# bluetooth_adapter.net
KiCad netlist of a schematic drawn in EAGLE
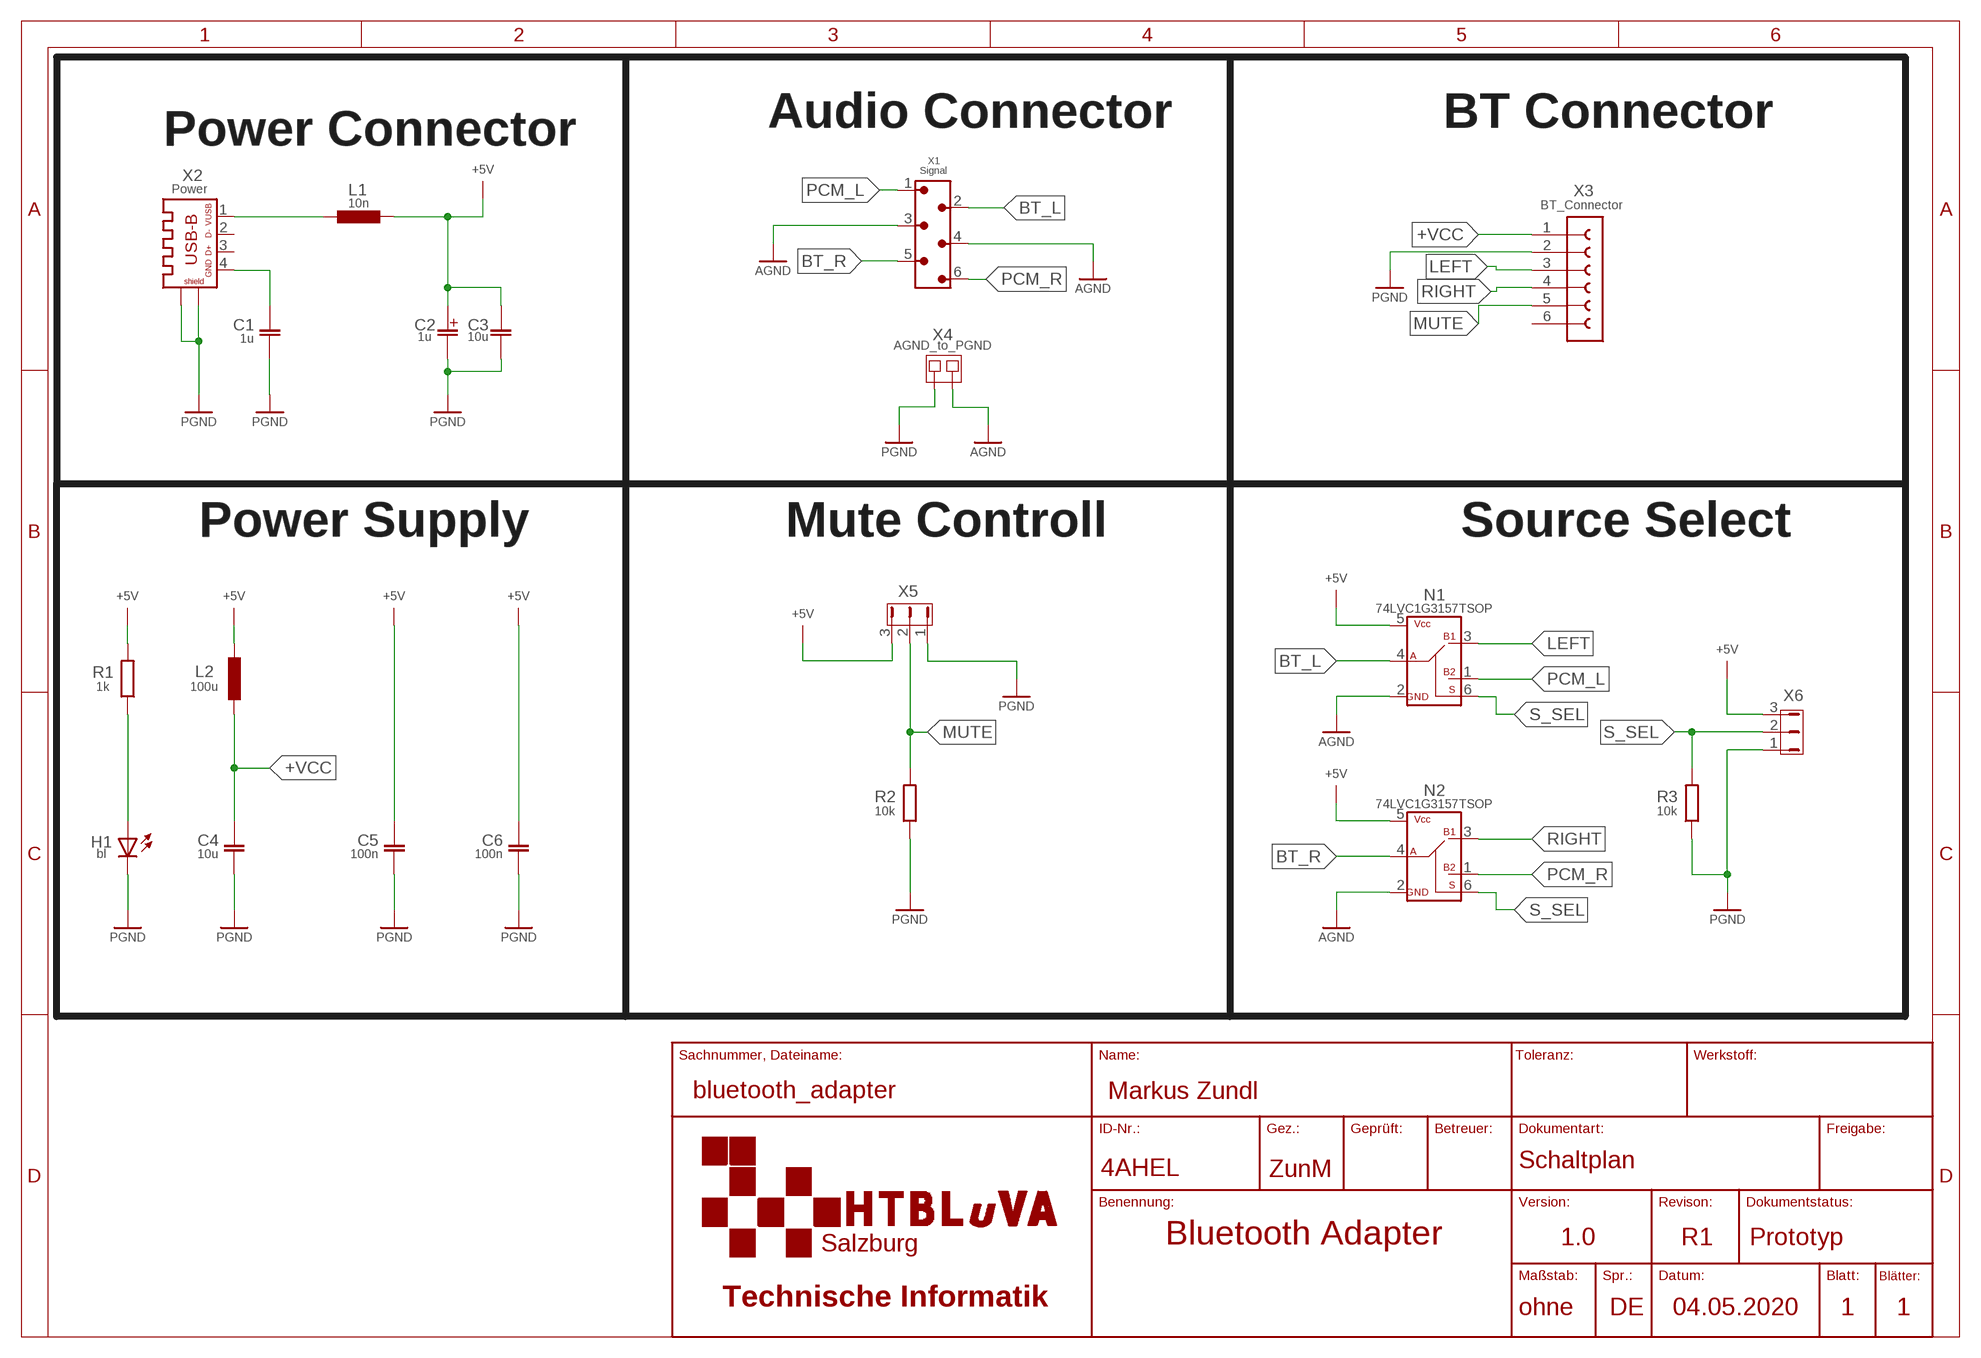
[diagram p0: schematic, sheet 1]

(export (version "E")
  (design (tool "Eeschema 10.0.6"))
  (components
    (comp (ref "C1")
      (value "1u")
      (footprint "eagle-import:C3216")
      (libsource (lib "eagle-import") (part "C-EUC3216"))
    )
    (comp (ref "C2")
      (value "1u")
      (footprint "eagle-import:A_3216-18R")
      (libsource (lib "eagle-import") (part "CPOL-EUA/3216-18R"))
    )
    (comp (ref "C3")
      (value "10u")
      (footprint "eagle-import:C3216")
      (libsource (lib "eagle-import") (part "C-EUC3216"))
    )
    (comp (ref "C4")
      (value "10u")
      (footprint "eagle-import:C3216")
      (libsource (lib "eagle-import") (part "C-EUC3216"))
    )
    (comp (ref "C5")
      (value "100n")
      (footprint "eagle-import:C3216")
      (libsource (lib "eagle-import") (part "C-EUC3216"))
    )
    (comp (ref "C6")
      (value "100n")
      (footprint "eagle-import:C3216")
      (libsource (lib "eagle-import") (part "C-EUC3216"))
    )
    (comp (ref "H1")
      (value "bl")
      (footprint "eagle-import:CHIPLED_0805")
      (libsource (lib "eagle-import") (part "LEDCHIPLED_0805"))
    )
    (comp (ref "L1")
      (value "10n")
      (footprint "eagle-import:L1210")
      (libsource (lib "eagle-import") (part "L-EUL1210"))
    )
    (comp (ref "L2")
      (value "100u")
      (footprint "eagle-import:L0805")
      (libsource (lib "eagle-import") (part "L-EUL0805"))
    )
    (comp (ref "N1")
      (value "74LVC1G3157TSOP")
      (footprint "eagle-import:TSOP6")
      (libsource (lib "eagle-import") (part "74LVC1G3157TSOP"))
    )
    (comp (ref "N2")
      (value "74LVC1G3157TSOP")
      (footprint "eagle-import:TSOP6")
      (libsource (lib "eagle-import") (part "74LVC1G3157TSOP"))
    )
    (comp (ref "R1")
      (value "1k")
      (footprint "eagle-import:R0805")
      (libsource (lib "eagle-import") (part "R-EU_R0805"))
    )
    (comp (ref "R2")
      (value "10k")
      (footprint "eagle-import:R0805")
      (libsource (lib "eagle-import") (part "R-EU_R0805"))
    )
    (comp (ref "R3")
      (value "10k")
      (footprint "eagle-import:R0805")
      (libsource (lib "eagle-import") (part "R-EU_R0805"))
    )
    (comp (ref "X1")
      (value "Signal")
      (footprint "eagle-import:690357100672")
      (libsource (lib "eagle-import") (part "WUERT_BUCHSE_6POL"))
    )
    (comp (ref "X2")
      (value "Power")
      (footprint "eagle-import:MYLIB_USB-B-LUM")
      (libsource (lib "eagle-import") (part "USB-B_432411"))
    )
    (comp (ref "X3")
      (value "BT_Connector")
      (footprint "eagle-import:MYCONNECTORS_FE-1X6_BDIA")
      (libsource (lib "eagle-import") (part "CONNECTORS_FEMHD-1X61X6_BDIA"))
    )
    (comp (ref "X4")
      (value "AGND_to_PGND")
      (footprint "eagle-import:MYLIB_SJ")
      (libsource (lib "eagle-import") (part "JUMPSMD1FACH-1"))
    )
    (comp (ref "X5")
      (value "JP2E")
      (footprint "eagle-import:MYLIB_JP2")
      (libsource (lib "eagle-import") (part "JP2E"))
    )
    (comp (ref "X6")
      (value "JP2E")
      (footprint "eagle-import:MYLIB_JP2")
      (libsource (lib "eagle-import") (part "JP2E"))
    )
  )
  (nets
    (net (code "1") (name "+5V") (class "Default")
      (node (ref "C2") (pin "+") (pinfunction "+_+") (pintype "passive"))
      (node (ref "C3") (pin "1") (pinfunction "1_1") (pintype "passive"))
      (node (ref "C5") (pin "1") (pinfunction "1_1") (pintype "passive"))
      (node (ref "C6") (pin "1") (pinfunction "1_1") (pintype "passive"))
      (node (ref "L1") (pin "2") (pinfunction "2_2") (pintype "passive"))
      (node (ref "L2") (pin "2") (pinfunction "2_2") (pintype "passive"))
      (node (ref "N1") (pin "5") (pinfunction "VCC_5") (pintype "bidirectional"))
      (node (ref "N2") (pin "5") (pinfunction "VCC_5") (pintype "bidirectional"))
      (node (ref "R1") (pin "2") (pinfunction "2_2") (pintype "passive"))
      (node (ref "X5") (pin "3") (pinfunction "3_3") (pintype "passive"))
      (node (ref "X6") (pin "3") (pinfunction "3_3") (pintype "passive"))
    )
    (net (code "2") (name "+VCC") (class "Default")
      (node (ref "C4") (pin "1") (pinfunction "1_1") (pintype "passive"))
      (node (ref "L2") (pin "1") (pinfunction "1_1") (pintype "passive"))
      (node (ref "X3") (pin "1") (pinfunction "1_1") (pintype "passive"))
    )
    (net (code "3") (name "AGND") (class "Default")
      (node (ref "N1") (pin "2") (pinfunction "GND_2") (pintype "bidirectional"))
      (node (ref "N2") (pin "2") (pinfunction "GND_2") (pintype "bidirectional"))
      (node (ref "X1") (pin "3") (pinfunction "3_3") (pintype "passive"))
      (node (ref "X1") (pin "4") (pinfunction "4_4") (pintype "passive"))
      (node (ref "X4") (pin "2") (pinfunction "2_2") (pintype "passive"))
    )
    (net (code "4") (name "BT_L") (class "Default")
      (node (ref "N1") (pin "4") (pinfunction "A_4") (pintype "bidirectional"))
      (node (ref "X1") (pin "2") (pinfunction "2_2") (pintype "passive"))
    )
    (net (code "5") (name "BT_R") (class "Default")
      (node (ref "N2") (pin "4") (pinfunction "A_4") (pintype "bidirectional"))
      (node (ref "X1") (pin "5") (pinfunction "5_5") (pintype "passive"))
    )
    (net (code "6") (name "LEFT") (class "Default")
      (node (ref "N1") (pin "3") (pinfunction "B1_3") (pintype "bidirectional"))
      (node (ref "X3") (pin "3") (pinfunction "3_3") (pintype "passive"))
    )
    (net (code "7") (name "MUTE") (class "Default")
      (node (ref "R2") (pin "2") (pinfunction "2_2") (pintype "passive"))
      (node (ref "X3") (pin "5") (pinfunction "5_5") (pintype "passive"))
      (node (ref "X5") (pin "2") (pinfunction "2_2") (pintype "passive"))
    )
    (net (code "8") (name "Net-(C1-Pad1)") (class "Default")
      (node (ref "C1") (pin "1") (pinfunction "1_1") (pintype "passive"))
      (node (ref "X2") (pin "4") (pinfunction "4_4") (pintype "passive"))
    )
    (net (code "9") (name "Net-(H1-PadA)") (class "Default")
      (node (ref "H1") (pin "A") (pinfunction "A_A") (pintype "passive"))
      (node (ref "R1") (pin "1") (pinfunction "1_1") (pintype "passive"))
    )
    (net (code "10") (name "Net-(L1-Pad1)") (class "Default")
      (node (ref "L1") (pin "1") (pinfunction "1_1") (pintype "passive"))
      (node (ref "X2") (pin "1") (pinfunction "1_1") (pintype "passive"))
    )
    (net (code "11") (name "PCM_L") (class "Default")
      (node (ref "N1") (pin "1") (pinfunction "B2_1") (pintype "bidirectional"))
      (node (ref "X1") (pin "1") (pinfunction "1_1") (pintype "passive"))
    )
    (net (code "12") (name "PCM_R") (class "Default")
      (node (ref "N2") (pin "1") (pinfunction "B2_1") (pintype "bidirectional"))
      (node (ref "X1") (pin "6") (pinfunction "6_6") (pintype "passive"))
    )
    (net (code "13") (name "PGND") (class "Default")
      (node (ref "C1") (pin "2") (pinfunction "2_2") (pintype "passive"))
      (node (ref "C2") (pin "-") (pinfunction "-_-") (pintype "passive"))
      (node (ref "C3") (pin "2") (pinfunction "2_2") (pintype "passive"))
      (node (ref "C4") (pin "2") (pinfunction "2_2") (pintype "passive"))
      (node (ref "C5") (pin "2") (pinfunction "2_2") (pintype "passive"))
      (node (ref "C6") (pin "2") (pinfunction "2_2") (pintype "passive"))
      (node (ref "H1") (pin "C") (pinfunction "C_C") (pintype "passive"))
      (node (ref "R2") (pin "1") (pinfunction "1_1") (pintype "passive"))
      (node (ref "R3") (pin "1") (pinfunction "1_1") (pintype "passive"))
      (node (ref "X2") (pin "SH@1") (pinfunction "SH1_SH@1") (pintype "passive"))
      (node (ref "X2") (pin "SH@2") (pinfunction "SH2_SH@2") (pintype "passive"))
      (node (ref "X3") (pin "2") (pinfunction "2_2") (pintype "passive"))
      (node (ref "X4") (pin "1") (pinfunction "1_1") (pintype "passive"))
      (node (ref "X5") (pin "1") (pinfunction "1_1") (pintype "passive"))
      (node (ref "X6") (pin "1") (pinfunction "1_1") (pintype "passive"))
    )
    (net (code "14") (name "RIGHT") (class "Default")
      (node (ref "N2") (pin "3") (pinfunction "B1_3") (pintype "bidirectional"))
      (node (ref "X3") (pin "4") (pinfunction "4_4") (pintype "passive"))
    )
    (net (code "15") (name "S_SEL") (class "Default")
      (node (ref "N1") (pin "6") (pinfunction "S_6") (pintype "bidirectional"))
      (node (ref "N2") (pin "6") (pinfunction "S_6") (pintype "bidirectional"))
      (node (ref "R3") (pin "2") (pinfunction "2_2") (pintype "passive"))
      (node (ref "X6") (pin "2") (pinfunction "2_2") (pintype "passive"))
    )
    (net (code "16") (name "unconnected-(X2-Pad2)") (class "Default")
      (node (ref "X2") (pin "2") (pinfunction "2_2") (pintype "passive"))
    )
    (net (code "17") (name "unconnected-(X2-Pad3)") (class "Default")
      (node (ref "X2") (pin "3") (pinfunction "3_3") (pintype "passive"))
    )
    (net (code "18") (name "unconnected-(X3-Pad6)") (class "Default")
      (node (ref "X3") (pin "6") (pinfunction "6_6") (pintype "passive"))
    )
  )
)
